# LockNFC.net
KiCad netlist of a schematic drawn in EAGLE
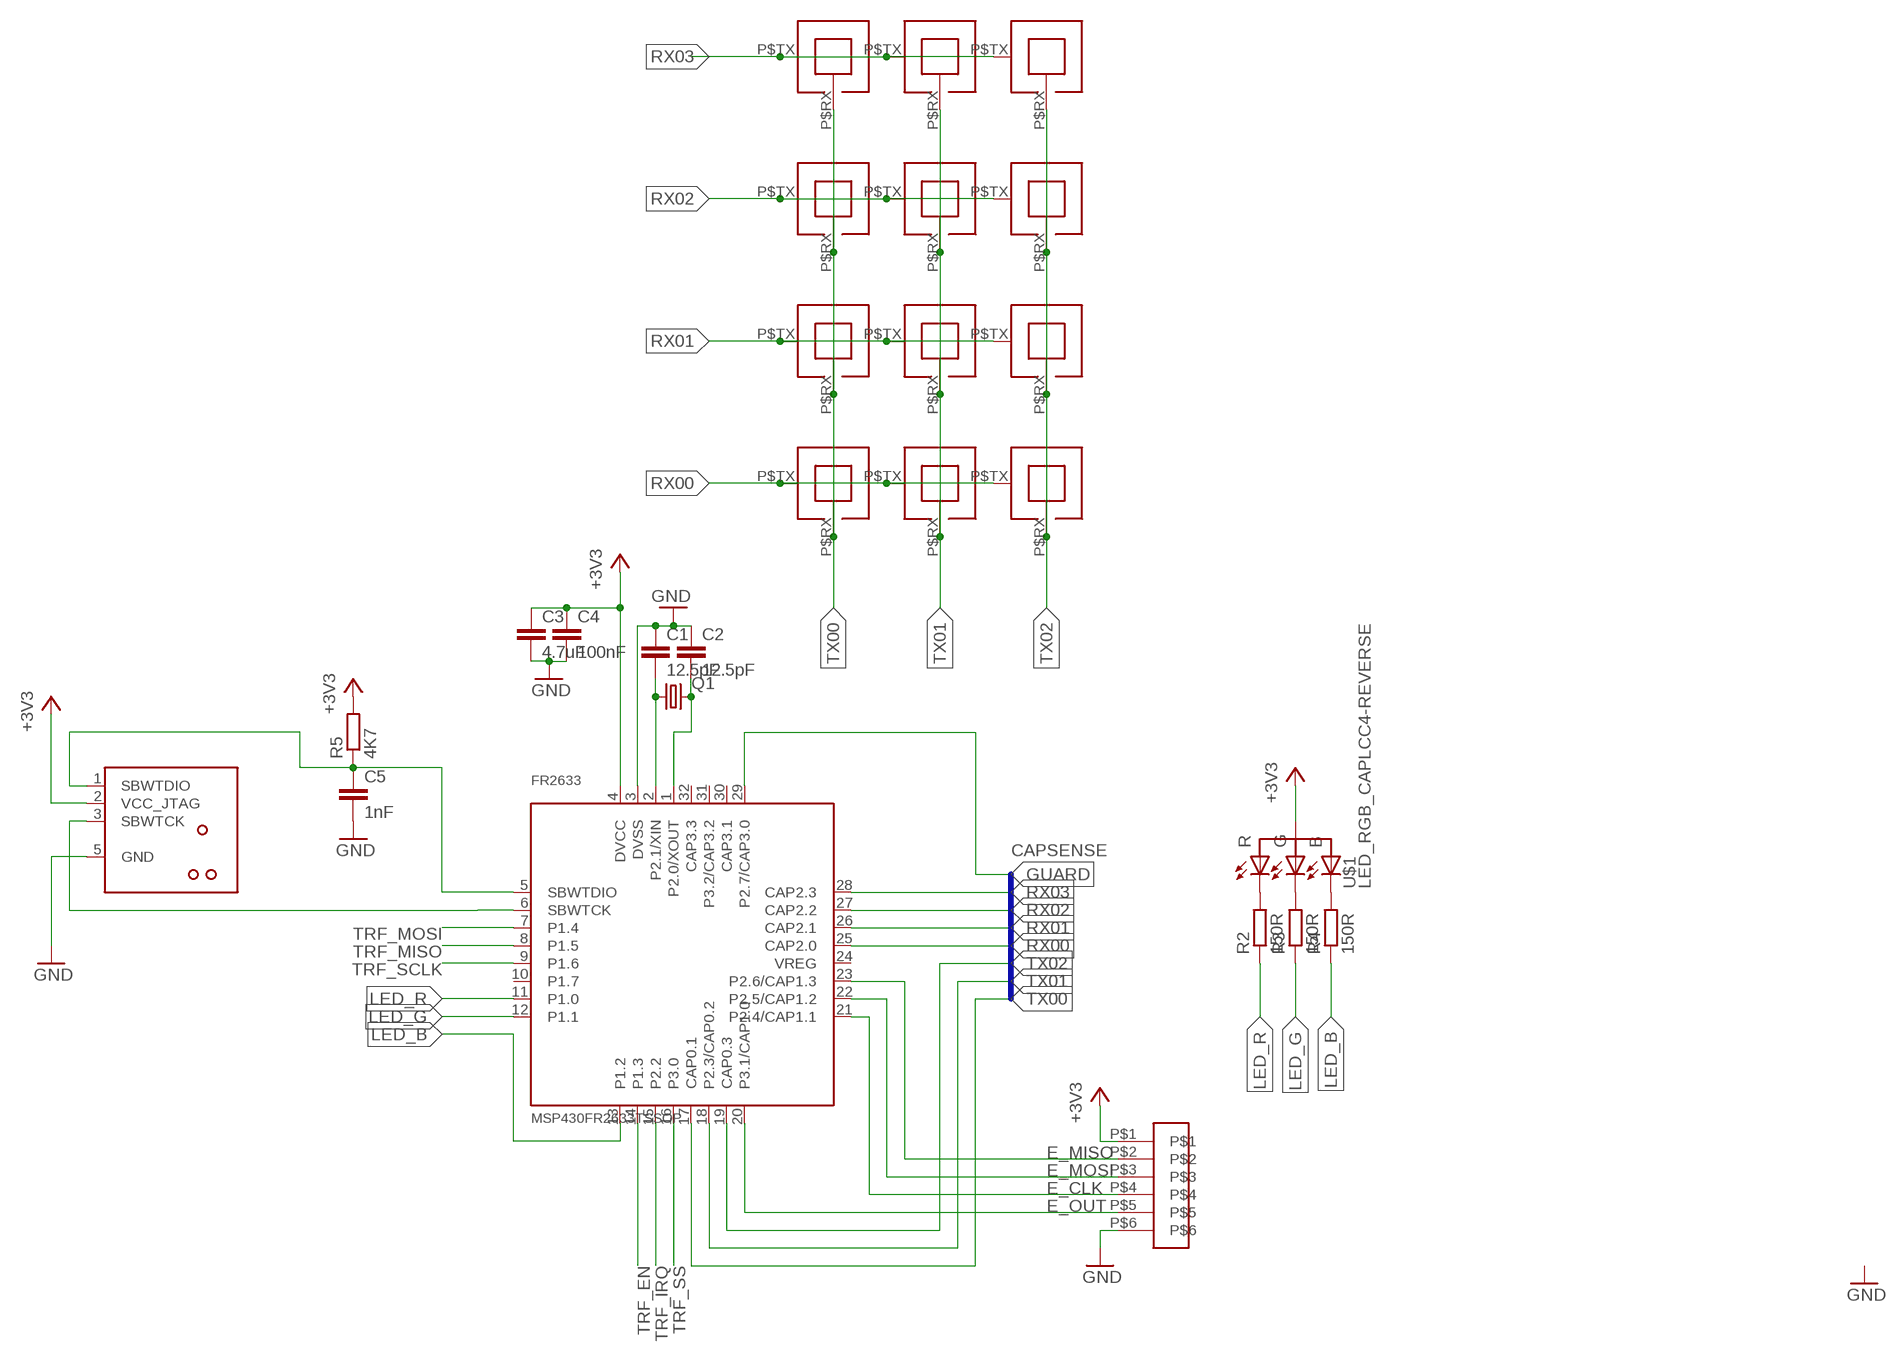
[diagram p0: schematic, sheet 1]
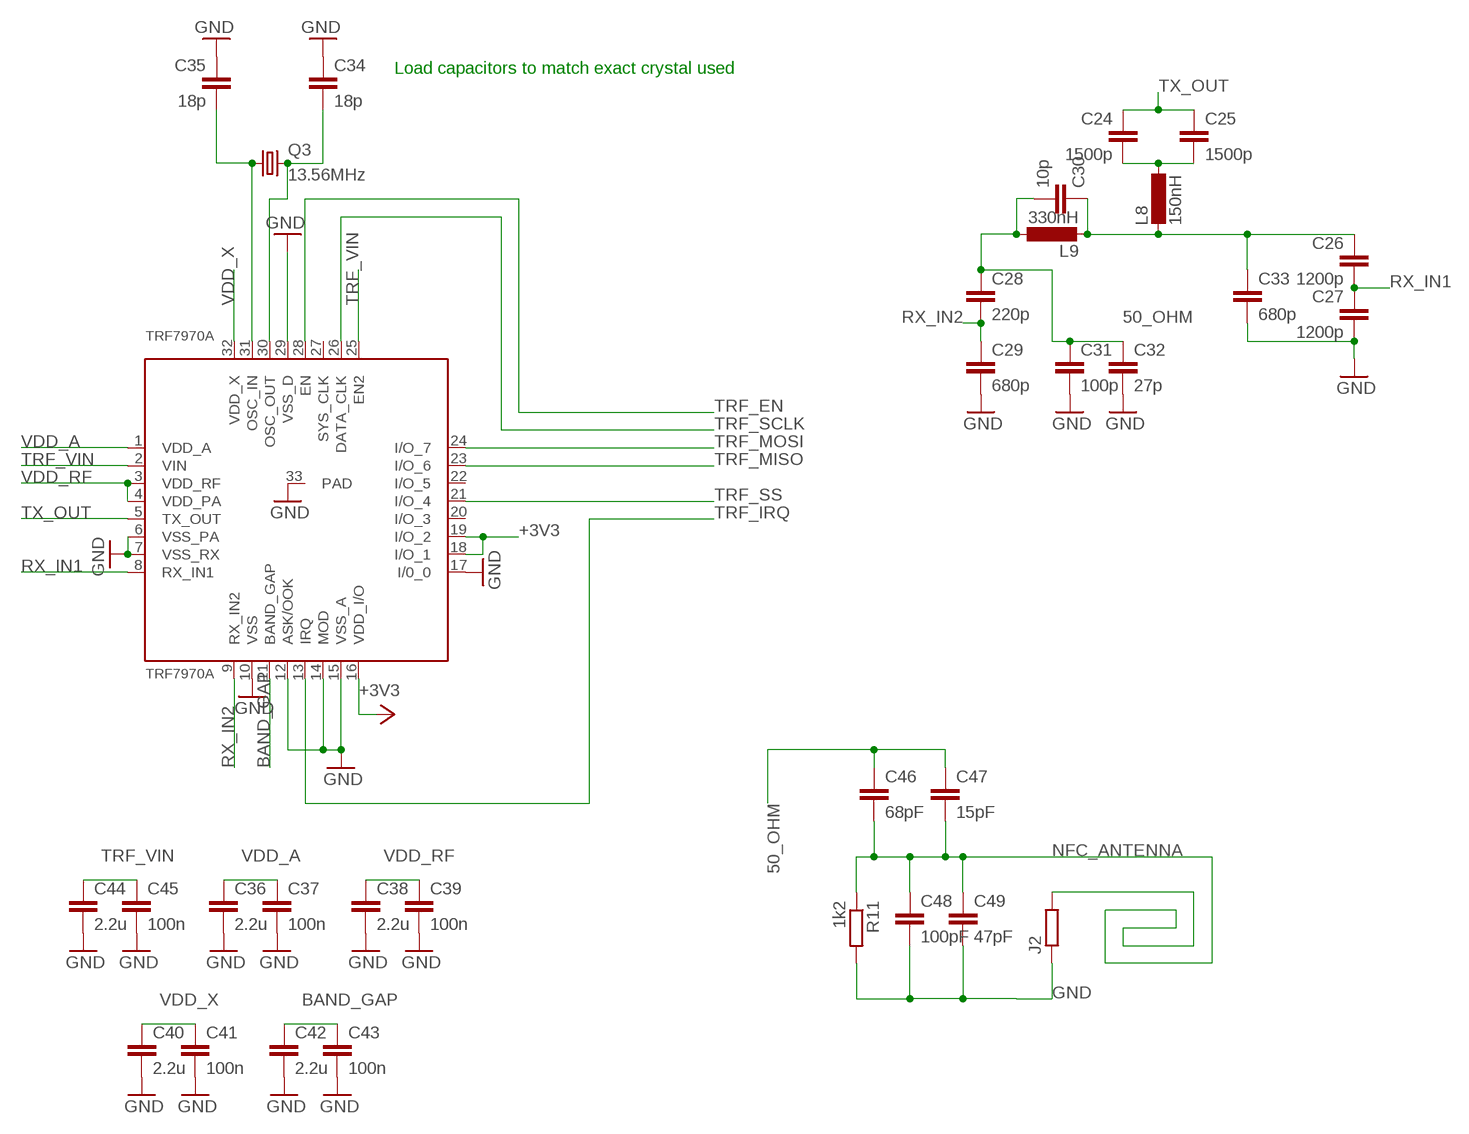
[diagram p1: schematic, sheet 2]

(export (version "E")
  (design (tool "Eeschema 10.0.6"))
  (components
    (comp (ref "C1")
      (value "12.5pF")
      (footprint "eagle-import:C0805")
      (libsource (lib "eagle-import") (part "C-EU_C0805"))
    )
    (comp (ref "C2")
      (value "12.5pF")
      (footprint "eagle-import:C0805")
      (libsource (lib "eagle-import") (part "C-EU_C0805"))
    )
    (comp (ref "C3")
      (value "4.7uF")
      (footprint "eagle-import:C0805")
      (libsource (lib "eagle-import") (part "C-EU_C0805"))
    )
    (comp (ref "C4")
      (value "100nF")
      (footprint "eagle-import:C0805")
      (libsource (lib "eagle-import") (part "C-EU_C0805"))
    )
    (comp (ref "C5")
      (value "1nF")
      (footprint "eagle-import:C0805")
      (libsource (lib "eagle-import") (part "C-EU_C0805"))
    )
    (comp (ref "FR2633")
      (value "MSP430FR2633TSSOP")
      (footprint "eagle-import:TSSOP(DA)32")
      (libsource (lib "eagle-import") (part "MSP430FR2633TSSOP"))
    )
    (comp (ref "J1")
      (value "TC2030-MSP430-NO-UART-NL")
      (footprint "eagle-import:TC2030-MSP430-NL-NO-UART")
      (libsource (lib "eagle-import") (part "TC2030-MSP430-NO-UART-NL"))
    )
    (comp (ref "Q1")
      (value "CRYSTALFC-135")
      (footprint "eagle-import:FC-135")
      (libsource (lib "eagle-import") (part "CRYSTALFC-135"))
    )
    (comp (ref "R2")
      (value "150R")
      (footprint "eagle-import:R0603")
      (libsource (lib "eagle-import") (part "R-EU_R0603"))
    )
    (comp (ref "R3")
      (value "150R")
      (footprint "eagle-import:R0603")
      (libsource (lib "eagle-import") (part "R-EU_R0603"))
    )
    (comp (ref "R4")
      (value "150R")
      (footprint "eagle-import:R0603")
      (libsource (lib "eagle-import") (part "R-EU_R0603"))
    )
    (comp (ref "R5")
      (value "4K7")
      (footprint "eagle-import:R0603")
      (libsource (lib "eagle-import") (part "R-EU_R0603"))
    )
    (comp (ref "U$1")
      (value "LED_RGB_CAPLCC4-REVERSE")
      (footprint "eagle-import:PLCC4-REVERSE")
      (libsource (lib "eagle-import") (part "LED_RGB_CAPLCC4-REVERSE"))
    )
    (comp (ref "U$2")
      (value "CAP_MUTUAL_SMALL")
      (footprint "eagle-import:CAP_MUTUAL_SMALL")
      (libsource (lib "eagle-import") (part "CAP_MUTUAL_SMALL"))
    )
    (comp (ref "U$3")
      (value "CAP_MUTUAL_SMALL")
      (footprint "eagle-import:CAP_MUTUAL_SMALL")
      (libsource (lib "eagle-import") (part "CAP_MUTUAL_SMALL"))
    )
    (comp (ref "U$4")
      (value "CAP_MUTUAL_SMALL")
      (footprint "eagle-import:CAP_MUTUAL_SMALL")
      (libsource (lib "eagle-import") (part "CAP_MUTUAL_SMALL"))
    )
    (comp (ref "U$5")
      (value "CAP_MUTUAL_SMALL")
      (footprint "eagle-import:CAP_MUTUAL_SMALL")
      (libsource (lib "eagle-import") (part "CAP_MUTUAL_SMALL"))
    )
    (comp (ref "U$6")
      (value "CAP_MUTUAL_SMALL")
      (footprint "eagle-import:CAP_MUTUAL_SMALL")
      (libsource (lib "eagle-import") (part "CAP_MUTUAL_SMALL"))
    )
    (comp (ref "U$7")
      (value "CAP_MUTUAL_SMALL")
      (footprint "eagle-import:CAP_MUTUAL_SMALL")
      (libsource (lib "eagle-import") (part "CAP_MUTUAL_SMALL"))
    )
    (comp (ref "U$8")
      (value "CAP_MUTUAL_SMALL")
      (footprint "eagle-import:CAP_MUTUAL_SMALL")
      (libsource (lib "eagle-import") (part "CAP_MUTUAL_SMALL"))
    )
    (comp (ref "U$9")
      (value "CAP_MUTUAL_SMALL")
      (footprint "eagle-import:CAP_MUTUAL_SMALL")
      (libsource (lib "eagle-import") (part "CAP_MUTUAL_SMALL"))
    )
    (comp (ref "U$10")
      (value "CAP_MUTUAL_SMALL")
      (footprint "eagle-import:CAP_MUTUAL_SMALL")
      (libsource (lib "eagle-import") (part "CAP_MUTUAL_SMALL"))
    )
    (comp (ref "U$11")
      (value "CAP_MUTUAL_SMALL")
      (footprint "eagle-import:CAP_MUTUAL_SMALL")
      (libsource (lib "eagle-import") (part "CAP_MUTUAL_SMALL"))
    )
    (comp (ref "U$12")
      (value "CAP_MUTUAL_SMALL")
      (footprint "eagle-import:CAP_MUTUAL_SMALL")
      (libsource (lib "eagle-import") (part "CAP_MUTUAL_SMALL"))
    )
    (comp (ref "U$13")
      (value "CAP_MUTUAL_SMALL")
      (footprint "eagle-import:CAP_MUTUAL_SMALL")
      (libsource (lib "eagle-import") (part "CAP_MUTUAL_SMALL"))
    )
    (comp (ref "U$14")
      (value "1X6_SMD_HEADER")
      (footprint "eagle-import:1X6-SMD-1.27MM")
      (libsource (lib "eagle-import") (part "1X6_SMD_HEADER"))
    )
    (comp (ref "C24")
      (value "1500p")
      (footprint "eagle-import:C0805")
      (libsource (lib "eagle-import") (part "C-EUC0805"))
    )
    (comp (ref "C25")
      (value "1500p")
      (footprint "eagle-import:C0805")
      (libsource (lib "eagle-import") (part "C-EUC0805"))
    )
    (comp (ref "C26")
      (value "1200p")
      (footprint "eagle-import:C0805")
      (libsource (lib "eagle-import") (part "C-EUC0805"))
    )
    (comp (ref "C27")
      (value "1200p")
      (footprint "eagle-import:C0805")
      (libsource (lib "eagle-import") (part "C-EUC0805"))
    )
    (comp (ref "C28")
      (value "220p")
      (footprint "eagle-import:C0805")
      (libsource (lib "eagle-import") (part "C-EUC0805"))
    )
    (comp (ref "C29")
      (value "680p")
      (footprint "eagle-import:C0805")
      (libsource (lib "eagle-import") (part "C-EUC0805"))
    )
    (comp (ref "C30")
      (value "10p")
      (footprint "eagle-import:C0805")
      (libsource (lib "eagle-import") (part "C-EUC0805"))
    )
    (comp (ref "C31")
      (value "100p")
      (footprint "eagle-import:C0805")
      (libsource (lib "eagle-import") (part "C-EUC0805"))
    )
    (comp (ref "C32")
      (value "27p")
      (footprint "eagle-import:C0805")
      (libsource (lib "eagle-import") (part "C-EUC0805"))
    )
    (comp (ref "C33")
      (value "680p")
      (footprint "eagle-import:C0805")
      (libsource (lib "eagle-import") (part "C-EUC0805"))
    )
    (comp (ref "C34")
      (value "18p")
      (footprint "eagle-import:C0805")
      (libsource (lib "eagle-import") (part "FredMiscellaneous_C-EU_C0805"))
    )
    (comp (ref "C35")
      (value "18p")
      (footprint "eagle-import:C0805")
      (libsource (lib "eagle-import") (part "FredMiscellaneous_C-EU_C0805"))
    )
    (comp (ref "C36")
      (value "2.2u")
      (footprint "eagle-import:C0805")
      (libsource (lib "eagle-import") (part "FredMiscellaneous_C-EU_C0805"))
    )
    (comp (ref "C37")
      (value "100n")
      (footprint "eagle-import:C0805")
      (libsource (lib "eagle-import") (part "FredMiscellaneous_C-EU_C0805"))
    )
    (comp (ref "C38")
      (value "2.2u")
      (footprint "eagle-import:C0805")
      (libsource (lib "eagle-import") (part "FredMiscellaneous_C-EU_C0805"))
    )
    (comp (ref "C39")
      (value "100n")
      (footprint "eagle-import:C0805")
      (libsource (lib "eagle-import") (part "FredMiscellaneous_C-EU_C0805"))
    )
    (comp (ref "C40")
      (value "2.2u")
      (footprint "eagle-import:C0805")
      (libsource (lib "eagle-import") (part "FredMiscellaneous_C-EU_C0805"))
    )
    (comp (ref "C41")
      (value "100n")
      (footprint "eagle-import:C0805")
      (libsource (lib "eagle-import") (part "FredMiscellaneous_C-EU_C0805"))
    )
    (comp (ref "C42")
      (value "2.2u")
      (footprint "eagle-import:C0805")
      (libsource (lib "eagle-import") (part "FredMiscellaneous_C-EU_C0805"))
    )
    (comp (ref "C43")
      (value "100n")
      (footprint "eagle-import:C0805")
      (libsource (lib "eagle-import") (part "FredMiscellaneous_C-EU_C0805"))
    )
    (comp (ref "C44")
      (value "2.2u")
      (footprint "eagle-import:C0805")
      (libsource (lib "eagle-import") (part "FredMiscellaneous_C-EU_C0805"))
    )
    (comp (ref "C45")
      (value "100n")
      (footprint "eagle-import:C0805")
      (libsource (lib "eagle-import") (part "FredMiscellaneous_C-EU_C0805"))
    )
    (comp (ref "C46")
      (value "68pF")
      (footprint "eagle-import:C0805")
      (libsource (lib "eagle-import") (part "C-EUC0805"))
    )
    (comp (ref "C47")
      (value "15pF")
      (footprint "eagle-import:C0805")
      (libsource (lib "eagle-import") (part "C-EUC0805"))
    )
    (comp (ref "C48")
      (value "100pF")
      (footprint "eagle-import:C0805")
      (libsource (lib "eagle-import") (part "C-EUC0805"))
    )
    (comp (ref "C49")
      (value "47pF")
      (footprint "eagle-import:C0805")
      (libsource (lib "eagle-import") (part "C-EUC0805"))
    )
    (comp (ref "J2")
      (value "R-EU_R0402")
      (footprint "eagle-import:R0402")
      (libsource (lib "eagle-import") (part "rcl_334_R-EU_R0402"))
    )
    (comp (ref "L8")
      (value "150nH")
      (footprint "eagle-import:L1008")
      (libsource (lib "eagle-import") (part "L-EU_L1008"))
    )
    (comp (ref "L9")
      (value "330nH")
      (footprint "eagle-import:L1008")
      (libsource (lib "eagle-import") (part "L-EU_L1008"))
    )
    (comp (ref "Q3")
      (value "13.56MHz")
      (footprint "eagle-import:CRYSTAL_TCX")
      (libsource (lib "eagle-import") (part "CRYSTAL_TXC"))
    )
    (comp (ref "R11")
      (value "1k2")
      (footprint "eagle-import:R0805")
      (libsource (lib "eagle-import") (part "FredMiscellaneous_R-EU_R0805"))
    )
    (comp (ref "TRF7970A")
      (value "TRF7970A")
      (footprint "eagle-import:QFN(RHB)32")
      (libsource (lib "eagle-import") (part "TRF7970A"))
    )
  )
  (nets
    (net (code "1") (name "+3V3") (class "Default")
      (node (ref "C3") (pin "1") (pinfunction "1_1") (pintype "passive"))
      (node (ref "C4") (pin "1") (pinfunction "1_1") (pintype "passive"))
      (node (ref "FR2633") (pin "4") (pinfunction "DVCC_4") (pintype "power_in"))
      (node (ref "J1") (pin "2") (pinfunction "VCC_JTAG_2") (pintype "power_in"))
      (node (ref "R5") (pin "2") (pinfunction "2_2") (pintype "passive"))
      (node (ref "TRF7970A") (pin "16") (pinfunction "VDD_I/O_16") (pintype "power_in"))
      (node (ref "TRF7970A") (pin "18") (pinfunction "I/O_1_18") (pintype "bidirectional"))
      (node (ref "TRF7970A") (pin "19") (pinfunction "I/O_2_19") (pintype "bidirectional"))
      (node (ref "U$1") (pin "P$2") (pinfunction "A_P$2") (pintype "passive"))
      (node (ref "U$14") (pin "P$1") (pinfunction "P$1_P$1") (pintype "bidirectional"))
    )
    (net (code "2") (name "50_OHM") (class "Default")
      (node (ref "C28") (pin "1") (pinfunction "1_1") (pintype "passive"))
      (node (ref "C30") (pin "2") (pinfunction "2_2") (pintype "passive"))
      (node (ref "C31") (pin "1") (pinfunction "1_1") (pintype "passive"))
      (node (ref "C32") (pin "1") (pinfunction "1_1") (pintype "passive"))
      (node (ref "C46") (pin "1") (pinfunction "1_1") (pintype "passive"))
      (node (ref "C47") (pin "1") (pinfunction "1_1") (pintype "passive"))
      (node (ref "L9") (pin "1") (pinfunction "1_1") (pintype "passive"))
    )
    (net (code "3") (name "BAND_GAP") (class "Default")
      (node (ref "C42") (pin "1") (pinfunction "1_1") (pintype "passive"))
      (node (ref "C43") (pin "1") (pinfunction "1_1") (pintype "passive"))
      (node (ref "TRF7970A") (pin "11") (pinfunction "BAND_GAP_11") (pintype "output"))
    )
    (net (code "4") (name "E_CLK") (class "Default")
      (node (ref "FR2633") (pin "21") (pinfunction "P2.4/CAP1.1_21") (pintype "bidirectional"))
      (node (ref "U$14") (pin "P$4") (pinfunction "P$4_P$4") (pintype "bidirectional"))
    )
    (net (code "5") (name "E_MISO") (class "Default")
      (node (ref "FR2633") (pin "23") (pinfunction "P2.6/CAP1.3_23") (pintype "bidirectional"))
      (node (ref "U$14") (pin "P$2") (pinfunction "P$2_P$2") (pintype "bidirectional"))
    )
    (net (code "6") (name "E_MOSI") (class "Default")
      (node (ref "FR2633") (pin "22") (pinfunction "P2.5/CAP1.2_22") (pintype "bidirectional"))
      (node (ref "U$14") (pin "P$3") (pinfunction "P$3_P$3") (pintype "bidirectional"))
    )
    (net (code "7") (name "E_OUT") (class "Default")
      (node (ref "FR2633") (pin "20") (pinfunction "P3.1/CAP1.0_20") (pintype "power_in"))
      (node (ref "U$14") (pin "P$5") (pinfunction "P$5_P$5") (pintype "bidirectional"))
    )
    (net (code "8") (name "GND") (class "Default")
      (node (ref "C1") (pin "1") (pinfunction "1_1") (pintype "passive"))
      (node (ref "C2") (pin "1") (pinfunction "1_1") (pintype "passive"))
      (node (ref "C27") (pin "2") (pinfunction "2_2") (pintype "passive"))
      (node (ref "C29") (pin "2") (pinfunction "2_2") (pintype "passive"))
      (node (ref "C3") (pin "2") (pinfunction "2_2") (pintype "passive"))
      (node (ref "C31") (pin "2") (pinfunction "2_2") (pintype "passive"))
      (node (ref "C32") (pin "2") (pinfunction "2_2") (pintype "passive"))
      (node (ref "C33") (pin "2") (pinfunction "2_2") (pintype "passive"))
      (node (ref "C34") (pin "1") (pinfunction "1_1") (pintype "passive"))
      (node (ref "C35") (pin "1") (pinfunction "1_1") (pintype "passive"))
      (node (ref "C36") (pin "2") (pinfunction "2_2") (pintype "passive"))
      (node (ref "C37") (pin "2") (pinfunction "2_2") (pintype "passive"))
      (node (ref "C38") (pin "2") (pinfunction "2_2") (pintype "passive"))
      (node (ref "C39") (pin "2") (pinfunction "2_2") (pintype "passive"))
      (node (ref "C4") (pin "2") (pinfunction "2_2") (pintype "passive"))
      (node (ref "C40") (pin "2") (pinfunction "2_2") (pintype "passive"))
      (node (ref "C41") (pin "2") (pinfunction "2_2") (pintype "passive"))
      (node (ref "C42") (pin "2") (pinfunction "2_2") (pintype "passive"))
      (node (ref "C43") (pin "2") (pinfunction "2_2") (pintype "passive"))
      (node (ref "C44") (pin "2") (pinfunction "2_2") (pintype "passive"))
      (node (ref "C45") (pin "2") (pinfunction "2_2") (pintype "passive"))
      (node (ref "C48") (pin "2") (pinfunction "2_2") (pintype "passive"))
      (node (ref "C49") (pin "2") (pinfunction "2_2") (pintype "passive"))
      (node (ref "C5") (pin "2") (pinfunction "2_2") (pintype "passive"))
      (node (ref "FR2633") (pin "3") (pinfunction "DVSS_3") (pintype "input"))
      (node (ref "J1") (pin "5") (pinfunction "GND_5") (pintype "power_in"))
      (node (ref "J2") (pin "1") (pinfunction "1_1") (pintype "passive"))
      (node (ref "R11") (pin "2") (pinfunction "2_2") (pintype "passive"))
      (node (ref "TRF7970A") (pin "10") (pinfunction "VSS_10") (pintype "power_in"))
      (node (ref "TRF7970A") (pin "12") (pinfunction "ASK/OOK_12") (pintype "bidirectional"))
      (node (ref "TRF7970A") (pin "14") (pinfunction "MOD_14") (pintype "input"))
      (node (ref "TRF7970A") (pin "15") (pinfunction "VSS_A_15") (pintype "power_in"))
      (node (ref "TRF7970A") (pin "17") (pinfunction "I/0_0_17") (pintype "bidirectional"))
      (node (ref "TRF7970A") (pin "29") (pinfunction "VSS_D_29") (pintype "power_in"))
      (node (ref "TRF7970A") (pin "33") (pinfunction "PAD_33") (pintype "power_in"))
      (node (ref "TRF7970A") (pin "6") (pinfunction "VSS_PA_6") (pintype "power_in"))
      (node (ref "TRF7970A") (pin "7") (pinfunction "VSS_RX_7") (pintype "power_in"))
      (node (ref "U$14") (pin "P$6") (pinfunction "P$6_P$6") (pintype "bidirectional"))
    )
    (net (code "9") (name "GUARD") (class "Default")
      (node (ref "FR2633") (pin "29") (pinfunction "P2.7/CAP3.0_29") (pintype "input"))
    )
    (net (code "10") (name "LED_B") (class "Default")
      (node (ref "FR2633") (pin "13") (pinfunction "P1.2_13") (pintype "input"))
      (node (ref "R4") (pin "1") (pinfunction "1_1") (pintype "passive"))
    )
    (net (code "11") (name "LED_G") (class "Default")
      (node (ref "FR2633") (pin "12") (pinfunction "P1.1_12") (pintype "input"))
      (node (ref "R3") (pin "1") (pinfunction "1_1") (pintype "passive"))
    )
    (net (code "12") (name "LED_R") (class "Default")
      (node (ref "FR2633") (pin "11") (pinfunction "P1.0_11") (pintype "power_in"))
      (node (ref "R2") (pin "1") (pinfunction "1_1") (pintype "passive"))
    )
    (net (code "13") (name "NFC_ANTENNA") (class "Default")
      (node (ref "C46") (pin "2") (pinfunction "2_2") (pintype "passive"))
      (node (ref "C47") (pin "2") (pinfunction "2_2") (pintype "passive"))
      (node (ref "C48") (pin "1") (pinfunction "1_1") (pintype "passive"))
      (node (ref "C49") (pin "1") (pinfunction "1_1") (pintype "passive"))
      (node (ref "J2") (pin "2") (pinfunction "2_2") (pintype "passive"))
      (node (ref "R11") (pin "1") (pinfunction "1_1") (pintype "passive"))
    )
    (net (code "14") (name "Net-(C24-Pad2)") (class "Default")
      (node (ref "C24") (pin "2") (pinfunction "2_2") (pintype "passive"))
      (node (ref "C25") (pin "2") (pinfunction "2_2") (pintype "passive"))
      (node (ref "L8") (pin "1") (pinfunction "1_1") (pintype "passive"))
    )
    (net (code "15") (name "Net-(C26-Pad1)") (class "Default")
      (node (ref "C26") (pin "1") (pinfunction "1_1") (pintype "passive"))
      (node (ref "C30") (pin "1") (pinfunction "1_1") (pintype "passive"))
      (node (ref "C33") (pin "1") (pinfunction "1_1") (pintype "passive"))
      (node (ref "L8") (pin "2") (pinfunction "2_2") (pintype "passive"))
      (node (ref "L9") (pin "2") (pinfunction "2_2") (pintype "passive"))
    )
    (net (code "16") (name "Net-(FR2633-P2.0{slash}XOUT)") (class "Default")
      (node (ref "C2") (pin "2") (pinfunction "2_2") (pintype "passive"))
      (node (ref "FR2633") (pin "1") (pinfunction "P2.0/XOUT_1") (pintype "power_in"))
      (node (ref "Q1") (pin "2") (pinfunction "2_2") (pintype "passive"))
    )
    (net (code "17") (name "Net-(FR2633-P2.1{slash}XIN)") (class "Default")
      (node (ref "C1") (pin "2") (pinfunction "2_2") (pintype "passive"))
      (node (ref "FR2633") (pin "2") (pinfunction "P2.1/XIN_2") (pintype "output"))
      (node (ref "Q1") (pin "1") (pinfunction "1_1") (pintype "passive"))
    )
    (net (code "18") (name "Net-(FR2633-SBWTCK)") (class "Default")
      (node (ref "FR2633") (pin "6") (pinfunction "SBWTCK_6") (pintype "power_in"))
      (node (ref "J1") (pin "3") (pinfunction "SBWTCK_3") (pintype "bidirectional"))
    )
    (net (code "19") (name "Net-(FR2633-SBWTDIO)") (class "Default")
      (node (ref "C5") (pin "1") (pinfunction "1_1") (pintype "passive"))
      (node (ref "FR2633") (pin "5") (pinfunction "SBWTDIO_5") (pintype "power_in"))
      (node (ref "J1") (pin "1") (pinfunction "SBWTDIO_1") (pintype "bidirectional"))
      (node (ref "R5") (pin "1") (pinfunction "1_1") (pintype "passive"))
    )
    (net (code "20") (name "Net-(TRF7970A-OSC_IN)") (class "Default")
      (node (ref "C35") (pin "2") (pinfunction "2_2") (pintype "passive"))
      (node (ref "Q3") (pin "1") (pinfunction "1_1") (pintype "passive"))
      (node (ref "TRF7970A") (pin "31") (pinfunction "OSC_IN_31") (pintype "input"))
    )
    (net (code "21") (name "Net-(TRF7970A-OSC_OUT)") (class "Default")
      (node (ref "C34") (pin "2") (pinfunction "2_2") (pintype "passive"))
      (node (ref "Q3") (pin "2") (pinfunction "2_2") (pintype "passive"))
      (node (ref "TRF7970A") (pin "30") (pinfunction "OSC_OUT_30") (pintype "output"))
    )
    (net (code "22") (name "Net-(U$1-C_BLUE)") (class "Default")
      (node (ref "R4") (pin "2") (pinfunction "2_2") (pintype "passive"))
      (node (ref "U$1") (pin "P$3") (pinfunction "C_BLUE_P$3") (pintype "passive"))
    )
    (net (code "23") (name "Net-(U$1-C_GREEN)") (class "Default")
      (node (ref "R3") (pin "2") (pinfunction "2_2") (pintype "passive"))
      (node (ref "U$1") (pin "P$4") (pinfunction "C_GREEN_P$4") (pintype "passive"))
    )
    (net (code "24") (name "Net-(U$1-C_RED)") (class "Default")
      (node (ref "R2") (pin "2") (pinfunction "2_2") (pintype "passive"))
      (node (ref "U$1") (pin "P$1") (pinfunction "C_RED_P$1") (pintype "passive"))
    )
    (net (code "25") (name "P1.7") (class "Default")
      (node (ref "FR2633") (pin "10") (pinfunction "P1.7_10") (pintype "power_in"))
    )
    (net (code "26") (name "RX00") (class "Default")
      (node (ref "FR2633") (pin "25") (pinfunction "CAP2.0_25") (pintype "bidirectional"))
      (node (ref "U$11") (pin "P$TX") (pinfunction "TX_P$TX") (pintype "bidirectional"))
      (node (ref "U$12") (pin "P$TX") (pinfunction "TX_P$TX") (pintype "bidirectional"))
      (node (ref "U$13") (pin "P$TX") (pinfunction "TX_P$TX") (pintype "bidirectional"))
    )
    (net (code "27") (name "RX01") (class "Default")
      (node (ref "FR2633") (pin "26") (pinfunction "CAP2.1_26") (pintype "bidirectional"))
      (node (ref "U$10") (pin "P$TX") (pinfunction "TX_P$TX") (pintype "bidirectional"))
      (node (ref "U$8") (pin "P$TX") (pinfunction "TX_P$TX") (pintype "bidirectional"))
      (node (ref "U$9") (pin "P$TX") (pinfunction "TX_P$TX") (pintype "bidirectional"))
    )
    (net (code "28") (name "RX02") (class "Default")
      (node (ref "FR2633") (pin "27") (pinfunction "CAP2.2_27") (pintype "bidirectional"))
      (node (ref "U$5") (pin "P$TX") (pinfunction "TX_P$TX") (pintype "bidirectional"))
      (node (ref "U$6") (pin "P$TX") (pinfunction "TX_P$TX") (pintype "bidirectional"))
      (node (ref "U$7") (pin "P$TX") (pinfunction "TX_P$TX") (pintype "bidirectional"))
    )
    (net (code "29") (name "RX03") (class "Default")
      (node (ref "FR2633") (pin "28") (pinfunction "CAP2.3_28") (pintype "bidirectional"))
      (node (ref "U$2") (pin "P$TX") (pinfunction "TX_P$TX") (pintype "bidirectional"))
      (node (ref "U$3") (pin "P$TX") (pinfunction "TX_P$TX") (pintype "bidirectional"))
      (node (ref "U$4") (pin "P$TX") (pinfunction "TX_P$TX") (pintype "bidirectional"))
    )
    (net (code "30") (name "RX_IN1") (class "Default")
      (node (ref "C26") (pin "2") (pinfunction "2_2") (pintype "passive"))
      (node (ref "C27") (pin "1") (pinfunction "1_1") (pintype "passive"))
      (node (ref "TRF7970A") (pin "8") (pinfunction "RX_IN1_8") (pintype "input"))
    )
    (net (code "31") (name "RX_IN2") (class "Default")
      (node (ref "C28") (pin "2") (pinfunction "2_2") (pintype "passive"))
      (node (ref "C29") (pin "1") (pinfunction "1_1") (pintype "passive"))
      (node (ref "TRF7970A") (pin "9") (pinfunction "RX_IN2_9") (pintype "input"))
    )
    (net (code "32") (name "TRF_EN") (class "Default")
      (node (ref "FR2633") (pin "14") (pinfunction "P1.3_14") (pintype "power_in"))
      (node (ref "TRF7970A") (pin "28") (pinfunction "EN_28") (pintype "input"))
    )
    (net (code "33") (name "TRF_IRQ") (class "Default")
      (node (ref "FR2633") (pin "15") (pinfunction "P2.2_15") (pintype "output"))
      (node (ref "TRF7970A") (pin "13") (pinfunction "IRQ_13") (pintype "output"))
    )
    (net (code "34") (name "TRF_MISO") (class "Default")
      (node (ref "FR2633") (pin "8") (pinfunction "P1.5_8") (pintype "power_in"))
      (node (ref "TRF7970A") (pin "23") (pinfunction "I/O_6_23") (pintype "bidirectional"))
    )
    (net (code "35") (name "TRF_MOSI") (class "Default")
      (node (ref "FR2633") (pin "7") (pinfunction "P1.4_7") (pintype "power_in"))
      (node (ref "TRF7970A") (pin "24") (pinfunction "I/O_7_24") (pintype "bidirectional"))
    )
    (net (code "36") (name "TRF_SCLK") (class "Default")
      (node (ref "FR2633") (pin "9") (pinfunction "P1.6_9") (pintype "output"))
      (node (ref "TRF7970A") (pin "26") (pinfunction "DATA_CLK_26") (pintype "input"))
    )
    (net (code "37") (name "TRF_SS") (class "Default")
      (node (ref "FR2633") (pin "16") (pinfunction "P3.0_16") (pintype "bidirectional"))
      (node (ref "TRF7970A") (pin "21") (pinfunction "I/O_4_21") (pintype "bidirectional"))
    )
    (net (code "38") (name "TRF_VIN") (class "Default")
      (node (ref "C44") (pin "1") (pinfunction "1_1") (pintype "passive"))
      (node (ref "C45") (pin "1") (pinfunction "1_1") (pintype "passive"))
      (node (ref "TRF7970A") (pin "2") (pinfunction "VIN_2") (pintype "power_in"))
      (node (ref "TRF7970A") (pin "25") (pinfunction "EN2_25") (pintype "input"))
    )
    (net (code "39") (name "TX00") (class "Default")
      (node (ref "FR2633") (pin "17") (pinfunction "CAP0.1_17") (pintype "output"))
      (node (ref "U$11") (pin "P$RX") (pinfunction "RX_P$RX") (pintype "bidirectional"))
      (node (ref "U$2") (pin "P$RX") (pinfunction "RX_P$RX") (pintype "bidirectional"))
      (node (ref "U$5") (pin "P$RX") (pinfunction "RX_P$RX") (pintype "bidirectional"))
      (node (ref "U$8") (pin "P$RX") (pinfunction "RX_P$RX") (pintype "bidirectional"))
    )
    (net (code "40") (name "TX01") (class "Default")
      (node (ref "FR2633") (pin "18") (pinfunction "P2.3/CAP0.2_18") (pintype "input"))
      (node (ref "U$12") (pin "P$RX") (pinfunction "RX_P$RX") (pintype "bidirectional"))
      (node (ref "U$3") (pin "P$RX") (pinfunction "RX_P$RX") (pintype "bidirectional"))
      (node (ref "U$6") (pin "P$RX") (pinfunction "RX_P$RX") (pintype "bidirectional"))
      (node (ref "U$9") (pin "P$RX") (pinfunction "RX_P$RX") (pintype "bidirectional"))
    )
    (net (code "41") (name "TX02") (class "Default")
      (node (ref "FR2633") (pin "19") (pinfunction "CAP0.3_19") (pintype "power_in"))
      (node (ref "U$10") (pin "P$RX") (pinfunction "RX_P$RX") (pintype "bidirectional"))
      (node (ref "U$13") (pin "P$RX") (pinfunction "RX_P$RX") (pintype "bidirectional"))
      (node (ref "U$4") (pin "P$RX") (pinfunction "RX_P$RX") (pintype "bidirectional"))
      (node (ref "U$7") (pin "P$RX") (pinfunction "RX_P$RX") (pintype "bidirectional"))
    )
    (net (code "42") (name "TX_OUT") (class "Default")
      (node (ref "C24") (pin "1") (pinfunction "1_1") (pintype "passive"))
      (node (ref "C25") (pin "1") (pinfunction "1_1") (pintype "passive"))
      (node (ref "TRF7970A") (pin "5") (pinfunction "TX_OUT_5") (pintype "output"))
    )
    (net (code "43") (name "VDD_A") (class "Default")
      (node (ref "C36") (pin "1") (pinfunction "1_1") (pintype "passive"))
      (node (ref "C37") (pin "1") (pinfunction "1_1") (pintype "passive"))
      (node (ref "TRF7970A") (pin "1") (pinfunction "VDD_A_1") (pintype "power_in"))
    )
    (net (code "44") (name "VDD_RF") (class "Default")
      (node (ref "C38") (pin "1") (pinfunction "1_1") (pintype "passive"))
      (node (ref "C39") (pin "1") (pinfunction "1_1") (pintype "passive"))
      (node (ref "TRF7970A") (pin "3") (pinfunction "VDD_RF_3") (pintype "power_in"))
      (node (ref "TRF7970A") (pin "4") (pinfunction "VDD_PA_4") (pintype "power_in"))
    )
    (net (code "45") (name "VDD_X") (class "Default")
      (node (ref "C40") (pin "1") (pinfunction "1_1") (pintype "passive"))
      (node (ref "C41") (pin "1") (pinfunction "1_1") (pintype "passive"))
      (node (ref "TRF7970A") (pin "32") (pinfunction "VDD_X_32") (pintype "power_in"))
    )
    (net (code "46") (name "unconnected-(FR2633-CAP3.1-Pad30)") (class "Default")
      (node (ref "FR2633") (pin "30") (pinfunction "CAP3.1_30") (pintype "input"))
    )
    (net (code "47") (name "unconnected-(FR2633-CAP3.3-Pad32)") (class "Default")
      (node (ref "FR2633") (pin "32") (pinfunction "CAP3.3_32") (pintype "input"))
    )
    (net (code "48") (name "unconnected-(FR2633-P3.2{slash}CAP3.2-Pad31)") (class "Default")
      (node (ref "FR2633") (pin "31") (pinfunction "P3.2/CAP3.2_31") (pintype "output"))
    )
    (net (code "49") (name "unconnected-(FR2633-VREG-Pad24)") (class "Default")
      (node (ref "FR2633") (pin "24") (pinfunction "VREG_24") (pintype "bidirectional"))
    )
    (net (code "50") (name "unconnected-(TRF7970A-I{slash}O_3-Pad20)") (class "Default")
      (node (ref "TRF7970A") (pin "20") (pinfunction "I/O_3_20") (pintype "bidirectional"))
    )
    (net (code "51") (name "unconnected-(TRF7970A-I{slash}O_5-Pad22)") (class "Default")
      (node (ref "TRF7970A") (pin "22") (pinfunction "I/O_5_22") (pintype "bidirectional"))
    )
    (net (code "52") (name "unconnected-(TRF7970A-SYS_CLK-Pad27)") (class "Default")
      (node (ref "TRF7970A") (pin "27") (pinfunction "SYS_CLK_27") (pintype "output"))
    )
  )
)
